# Interfaz_de_Usuario.net
KiCad netlist of a schematic drawn in Altium Designer
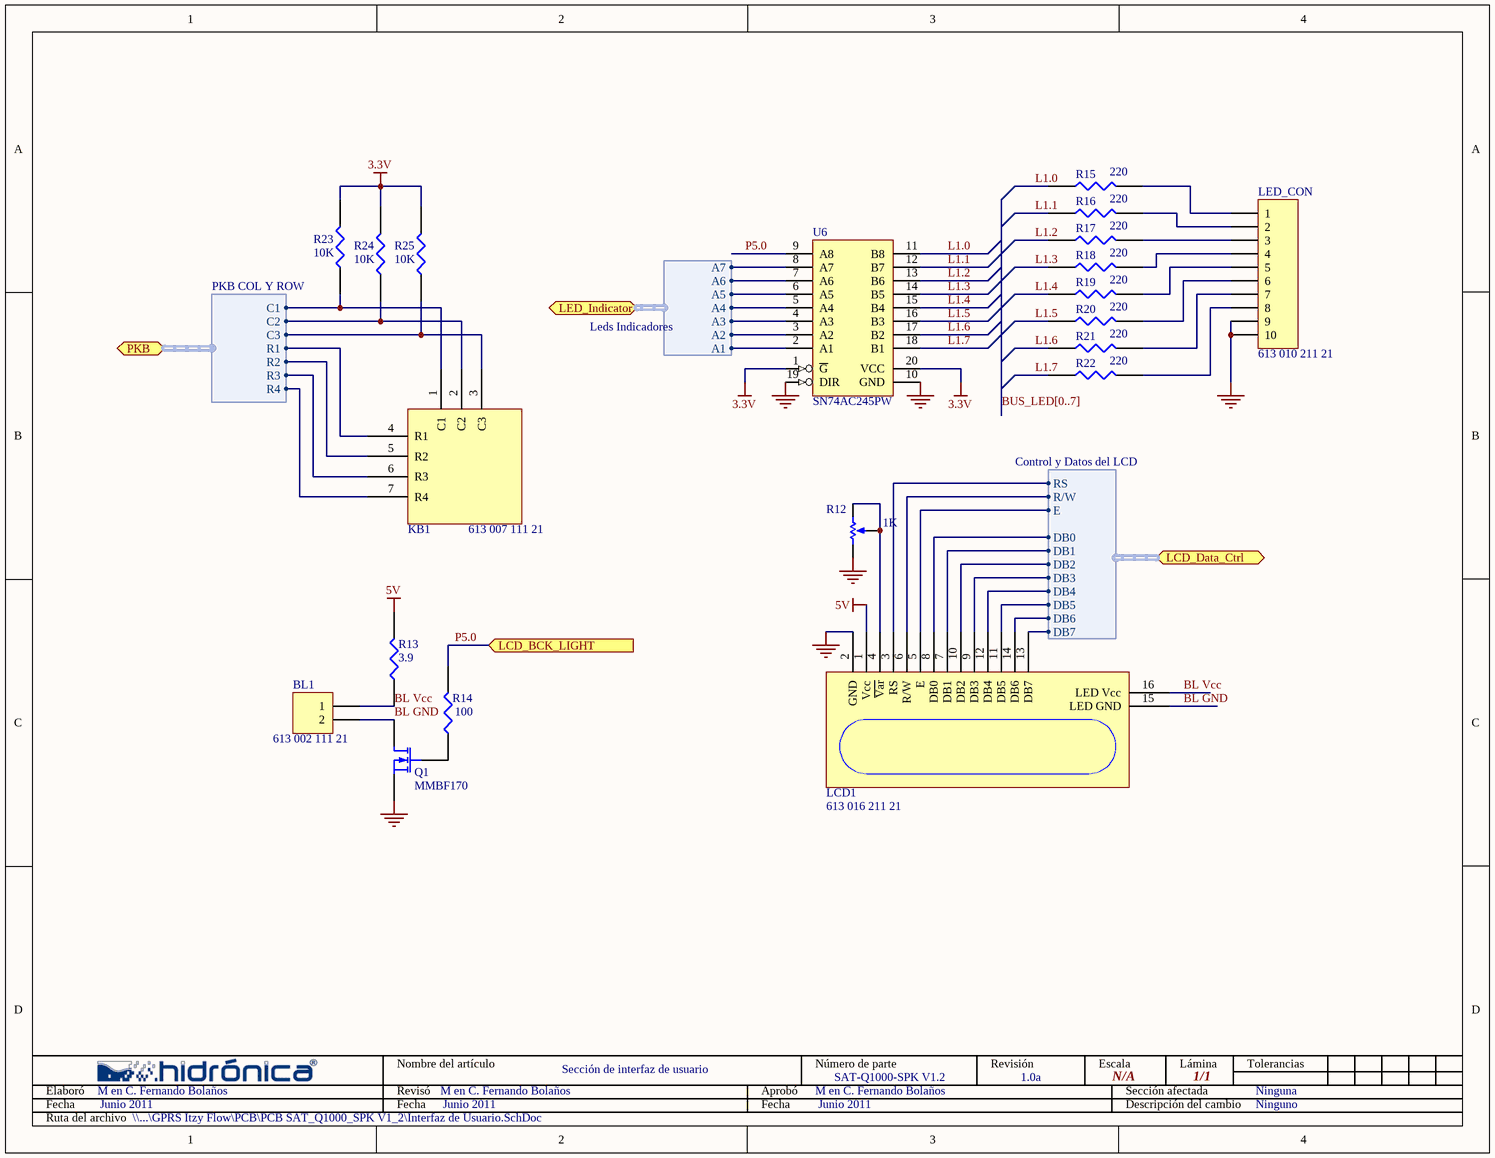
[diagram p0: Interfaz de Usuario.SchDoc]

(export (version "E")
  (design (tool "Eeschema 10.0.6"))
  (components
    (comp (ref "BL1")
      (value "613 002 111 21")
      (footprint "PIN2")
      (description "2.54mm Pin Header WR-PHD")
      (fields (field (name "PUBLISHER") "Altium Limited"))
      (libsource (lib "Miscellaneous Connectors") (part "Header 2"))
    )
    (comp (ref "KB1")
      (value "613 007 111 21")
      (footprint "HDR1X7")
      (description "2.54mm Pin Header WR-PHD")
      (fields (field (name "NUMERO DE PARTE") "613 007 111 21"))
      (libsource (lib "lib1") (part "Teclado 4x3"))
    )
    (comp (ref "LCD1")
      (value "613 016 211 21")
      (footprint "HDR2X8")
      (description "2.54mm Dual Pin Header WR-PHD")
      (libsource (lib "lib1") (part "LCD 2x20 P"))
    )
    (comp (ref "LED_CON")
      (value "613 010 211 21")
      (footprint "HDR2X5")
      (description "2.54mm Dual Pin Header WR-PHD")
      (fields (field (name "PUBLISHER") "Altium Limited"))
      (libsource (lib "Miscellaneous Connectors") (part "Header 10"))
    )
    (comp (ref "Q1")
      (value "MMBF170")
      (footprint "sot-23")
      (description "N-Channel MOSFET")
      (fields (field (name "PUBLISHER") "Altium Limited"))
      (libsource (lib "Miscellaneous Devices") (part "MOSFET-N"))
    )
    (comp (ref "R12")
      (value "1K")
      (footprint "TS63Y502K Res Var")
      (description "Potentiometer")
      (fields (field (name "PUBLISHER") "Altium Limited"))
      (libsource (lib "Miscellaneous Devices") (part "RPot"))
    )
    (comp (ref "R13")
      (value "3.9")
      (footprint "1206")
      (description "RESISTOR 3.9 OHM 1/4W 5% 1206")
      (libsource (lib "*") (part "RES1"))
    )
    (comp (ref "R14") (value "100") (footprint "1206") (libsource (lib "*") (part "RES1")))
    (comp (ref "R15")
      (value "220")
      (footprint "1206")
      (description "RES 220 OHM 1/4W 5% 1206 SMD")
      (libsource (lib "*") (part "RES1"))
    )
    (comp (ref "R16")
      (value "220")
      (footprint "1206")
      (description "RES 220 OHM 1/4W 5% 1206 SMD")
      (libsource (lib "*") (part "RES1"))
    )
    (comp (ref "R17")
      (value "220")
      (footprint "1206")
      (description "RES 220 OHM 1/4W 5% 1206 SMD")
      (libsource (lib "*") (part "RES1"))
    )
    (comp (ref "R18")
      (value "220")
      (footprint "1206")
      (description "RES 220 OHM 1/4W 5% 1206 SMD")
      (libsource (lib "*") (part "RES1"))
    )
    (comp (ref "R19")
      (value "220")
      (footprint "1206")
      (description "RES 220 OHM 1/4W 5% 1206 SMD")
      (libsource (lib "*") (part "RES1"))
    )
    (comp (ref "R20")
      (value "220")
      (footprint "1206")
      (description "RES 220 OHM 1/4W 5% 1206 SMD")
      (libsource (lib "*") (part "RES1"))
    )
    (comp (ref "R21")
      (value "220")
      (footprint "1206")
      (description "RES 220 OHM 1/4W 5% 1206 SMD")
      (libsource (lib "*") (part "RES1"))
    )
    (comp (ref "R22")
      (value "220")
      (footprint "1206")
      (description "RES 220 OHM 1/4W 5% 1206 SMD")
      (libsource (lib "*") (part "RES1"))
    )
    (comp (ref "R23")
      (value "10K")
      (footprint "1206")
      (description "RES 10K OHM 1/4W 5% 1206 SMD")
      (libsource (lib "*") (part "RES1"))
    )
    (comp (ref "R24")
      (value "10K")
      (footprint "1206")
      (description "RES 10K OHM 1/4W 5% 1206 SMD")
      (libsource (lib "*") (part "RES1"))
    )
    (comp (ref "R25")
      (value "10K")
      (footprint "1206")
      (description "RES 10K OHM 1/4W 5% 1206 SMD")
      (libsource (lib "*") (part "RES1"))
    )
    (comp (ref "U6")
      (value "SN74AC245PW")
      (footprint "TSSOP-20-PW")
      (libsource (lib "*") (part "SN74AC245PW"))
    )
  )
  (nets
    (net (code "20") (name "/A1") (class "Default")
      (node (ref "U6") (pin "2") (pinfunction "A1_2") (pintype "passive"))
    )
    (net (code "21") (name "/A2") (class "Default")
      (node (ref "U6") (pin "3") (pinfunction "A2_3") (pintype "passive"))
    )
    (net (code "22") (name "/A3") (class "Default")
      (node (ref "U6") (pin "4") (pinfunction "A3_4") (pintype "passive"))
    )
    (net (code "23") (name "/A4") (class "Default")
      (node (ref "U6") (pin "5") (pinfunction "A4_5") (pintype "passive"))
    )
    (net (code "24") (name "/A5") (class "Default")
      (node (ref "U6") (pin "6") (pinfunction "A5_6") (pintype "passive"))
    )
    (net (code "25") (name "/A6") (class "Default")
      (node (ref "U6") (pin "7") (pinfunction "A6_7") (pintype "passive"))
    )
    (net (code "26") (name "/A7") (class "Default")
      (node (ref "U6") (pin "8") (pinfunction "A7_8") (pintype "passive"))
    )
    (net (code "27") (name "/BL GND") (class "Default")
      (node (ref "BL1") (pin "2") (pinfunction "2_2") (pintype "passive"))
      (node (ref "LCD1") (pin "15") (pinfunction "LED_GND_15") (pintype "passive"))
      (node (ref "Q1") (pin "3") (pinfunction "D_3") (pintype "passive"))
    )
    (net (code "28") (name "/BL Vcc") (class "Default")
      (node (ref "BL1") (pin "1") (pinfunction "1_1") (pintype "passive"))
      (node (ref "LCD1") (pin "16") (pinfunction "LED_Vcc_16") (pintype "passive"))
      (node (ref "R13") (pin "1") (pinfunction "1_1") (pintype "passive"))
    )
    (net (code "30") (name "/C1") (class "Default")
      (node (ref "KB1") (pin "1") (pinfunction "C1_1") (pintype "passive"))
      (node (ref "R23") (pin "1") (pinfunction "1_1") (pintype "passive"))
    )
    (net (code "31") (name "/C2") (class "Default")
      (node (ref "KB1") (pin "2") (pinfunction "C2_2") (pintype "passive"))
      (node (ref "R24") (pin "1") (pinfunction "1_1") (pintype "passive"))
    )
    (net (code "32") (name "/C3") (class "Default")
      (node (ref "KB1") (pin "3") (pinfunction "C3_3") (pintype "passive"))
      (node (ref "R25") (pin "1") (pinfunction "1_1") (pintype "passive"))
    )
    (net (code "33") (name "/DB0") (class "Default")
      (node (ref "LCD1") (pin "8") (pinfunction "DB0_8") (pintype "passive"))
    )
    (net (code "34") (name "/DB1") (class "Default")
      (node (ref "LCD1") (pin "7") (pinfunction "DB1_7") (pintype "passive"))
    )
    (net (code "35") (name "/DB2") (class "Default")
      (node (ref "LCD1") (pin "10") (pinfunction "DB2_10") (pintype "passive"))
    )
    (net (code "36") (name "/DB3") (class "Default")
      (node (ref "LCD1") (pin "9") (pinfunction "DB3_9") (pintype "passive"))
    )
    (net (code "37") (name "/DB4") (class "Default")
      (node (ref "LCD1") (pin "12") (pinfunction "DB4_12") (pintype "passive"))
    )
    (net (code "38") (name "/DB5") (class "Default")
      (node (ref "LCD1") (pin "11") (pinfunction "DB5_11") (pintype "passive"))
    )
    (net (code "39") (name "/DB6") (class "Default")
      (node (ref "LCD1") (pin "14") (pinfunction "DB6_14") (pintype "passive"))
    )
    (net (code "40") (name "/DB7") (class "Default")
      (node (ref "LCD1") (pin "13") (pinfunction "DB7_13") (pintype "passive"))
    )
    (net (code "41") (name "/E") (class "Default")
      (node (ref "LCD1") (pin "5") (pinfunction "E_5") (pintype "passive"))
    )
    (net (code "42") (name "/L1.0") (class "Default")
      (node (ref "R15") (pin "1") (pinfunction "1_1") (pintype "passive"))
      (node (ref "U6") (pin "11") (pinfunction "B8_11") (pintype "passive"))
    )
    (net (code "43") (name "/L1.1") (class "Default")
      (node (ref "R16") (pin "1") (pinfunction "1_1") (pintype "passive"))
      (node (ref "U6") (pin "12") (pinfunction "B7_12") (pintype "tri_state"))
    )
    (net (code "44") (name "/L1.2") (class "Default")
      (node (ref "R17") (pin "1") (pinfunction "1_1") (pintype "passive"))
      (node (ref "U6") (pin "13") (pinfunction "B6_13") (pintype "passive"))
    )
    (net (code "45") (name "/L1.3") (class "Default")
      (node (ref "R18") (pin "1") (pinfunction "1_1") (pintype "passive"))
      (node (ref "U6") (pin "14") (pinfunction "B5_14") (pintype "tri_state"))
    )
    (net (code "46") (name "/L1.4") (class "Default")
      (node (ref "R19") (pin "1") (pinfunction "1_1") (pintype "passive"))
      (node (ref "U6") (pin "15") (pinfunction "B4_15") (pintype "passive"))
    )
    (net (code "47") (name "/L1.5") (class "Default")
      (node (ref "R20") (pin "1") (pinfunction "1_1") (pintype "passive"))
      (node (ref "U6") (pin "16") (pinfunction "B3_16") (pintype "tri_state"))
    )
    (net (code "48") (name "/L1.6") (class "Default")
      (node (ref "R21") (pin "1") (pinfunction "1_1") (pintype "passive"))
      (node (ref "U6") (pin "17") (pinfunction "B2_17") (pintype "passive"))
    )
    (net (code "49") (name "/L1.7") (class "Default")
      (node (ref "R22") (pin "1") (pinfunction "1_1") (pintype "passive"))
      (node (ref "U6") (pin "18") (pinfunction "B1_18") (pintype "tri_state"))
    )
    (net (code "50") (name "/P5.0") (class "Default")
      (node (ref "R14") (pin "2") (pinfunction "2_2") (pintype "passive"))
      (node (ref "U6") (pin "9") (pinfunction "A8_9") (pintype "passive"))
    )
    (net (code "51") (name "/R1") (class "Default")
      (node (ref "KB1") (pin "4") (pinfunction "R1_4") (pintype "passive"))
    )
    (net (code "52") (name "/R2") (class "Default")
      (node (ref "KB1") (pin "5") (pinfunction "R2_5") (pintype "passive"))
    )
    (net (code "53") (name "/R3") (class "Default")
      (node (ref "KB1") (pin "6") (pinfunction "R3_6") (pintype "passive"))
    )
    (net (code "54") (name "/R4") (class "Default")
      (node (ref "KB1") (pin "7") (pinfunction "R4_7") (pintype "passive"))
    )
    (net (code "55") (name "/RS") (class "Default")
      (node (ref "LCD1") (pin "3") (pinfunction "RS_3") (pintype "passive"))
    )
    (net (code "56") (name "/R{slash}W") (class "Default")
      (node (ref "LCD1") (pin "6") (pinfunction "R/W_6") (pintype "passive"))
    )
    (net (code "60") (name "3.3V") (class "Default")
      (node (ref "R23") (pin "2") (pinfunction "2_2") (pintype "passive"))
      (node (ref "R24") (pin "2") (pinfunction "2_2") (pintype "passive"))
      (node (ref "R25") (pin "2") (pinfunction "2_2") (pintype "passive"))
      (node (ref "U6") (pin "1") (pinfunction "~{G}_1") (pintype "input"))
      (node (ref "U6") (pin "20") (pinfunction "VCC_20") (pintype "power_in"))
    )
    (net (code "61") (name "5V") (class "Default")
      (node (ref "LCD1") (pin "1") (pinfunction "Vcc_1") (pintype "passive"))
      (node (ref "R13") (pin "2") (pinfunction "2_2") (pintype "passive"))
    )
    (net (code "62") (name "GND") (class "Default")
      (node (ref "LCD1") (pin "2") (pinfunction "GND_2") (pintype "passive"))
      (node (ref "LED_CON") (pin "10") (pinfunction "10_10") (pintype "passive"))
      (node (ref "LED_CON") (pin "9") (pinfunction "9_9") (pintype "passive"))
      (node (ref "Q1") (pin "2") (pinfunction "S_2") (pintype "passive"))
      (node (ref "R12") (pin "1") (pinfunction "TOP_1") (pintype "passive"))
      (node (ref "U6") (pin "10") (pinfunction "GND_10") (pintype "power_in"))
      (node (ref "U6") (pin "19") (pinfunction "DIR_19") (pintype "input"))
    )
    (net (code "63") (name "Net-(LCD1-~{Var})") (class "Default")
      (node (ref "LCD1") (pin "4") (pinfunction "~{Var}_4") (pintype "passive"))
      (node (ref "R12") (pin "2") (pinfunction "BOT_2") (pintype "passive"))
      (node (ref "R12") (pin "3") (pinfunction "TAP_3") (pintype "passive"))
    )
    (net (code "64") (name "Net-(LED_CON-Pad1)") (class "Default")
      (node (ref "LED_CON") (pin "1") (pinfunction "1_1") (pintype "passive"))
      (node (ref "R15") (pin "2") (pinfunction "2_2") (pintype "passive"))
    )
    (net (code "65") (name "Net-(LED_CON-Pad2)") (class "Default")
      (node (ref "LED_CON") (pin "2") (pinfunction "2_2") (pintype "passive"))
      (node (ref "R16") (pin "2") (pinfunction "2_2") (pintype "passive"))
    )
    (net (code "66") (name "Net-(LED_CON-Pad3)") (class "Default")
      (node (ref "LED_CON") (pin "3") (pinfunction "3_3") (pintype "passive"))
      (node (ref "R17") (pin "2") (pinfunction "2_2") (pintype "passive"))
    )
    (net (code "67") (name "Net-(LED_CON-Pad4)") (class "Default")
      (node (ref "LED_CON") (pin "4") (pinfunction "4_4") (pintype "passive"))
      (node (ref "R18") (pin "2") (pinfunction "2_2") (pintype "passive"))
    )
    (net (code "68") (name "Net-(LED_CON-Pad5)") (class "Default")
      (node (ref "LED_CON") (pin "5") (pinfunction "5_5") (pintype "passive"))
      (node (ref "R19") (pin "2") (pinfunction "2_2") (pintype "passive"))
    )
    (net (code "69") (name "Net-(LED_CON-Pad6)") (class "Default")
      (node (ref "LED_CON") (pin "6") (pinfunction "6_6") (pintype "passive"))
      (node (ref "R20") (pin "2") (pinfunction "2_2") (pintype "passive"))
    )
    (net (code "70") (name "Net-(LED_CON-Pad7)") (class "Default")
      (node (ref "LED_CON") (pin "7") (pinfunction "7_7") (pintype "passive"))
      (node (ref "R21") (pin "2") (pinfunction "2_2") (pintype "passive"))
    )
    (net (code "71") (name "Net-(LED_CON-Pad8)") (class "Default")
      (node (ref "LED_CON") (pin "8") (pinfunction "8_8") (pintype "passive"))
      (node (ref "R22") (pin "2") (pinfunction "2_2") (pintype "passive"))
    )
    (net (code "72") (name "Net-(Q1-G)") (class "Default")
      (node (ref "Q1") (pin "1") (pinfunction "G_1") (pintype "passive"))
      (node (ref "R14") (pin "1") (pinfunction "1_1") (pintype "passive"))
    )
  )
)
